# schematEle.net
KiCad netlist of a schematic drawn in EAGLE
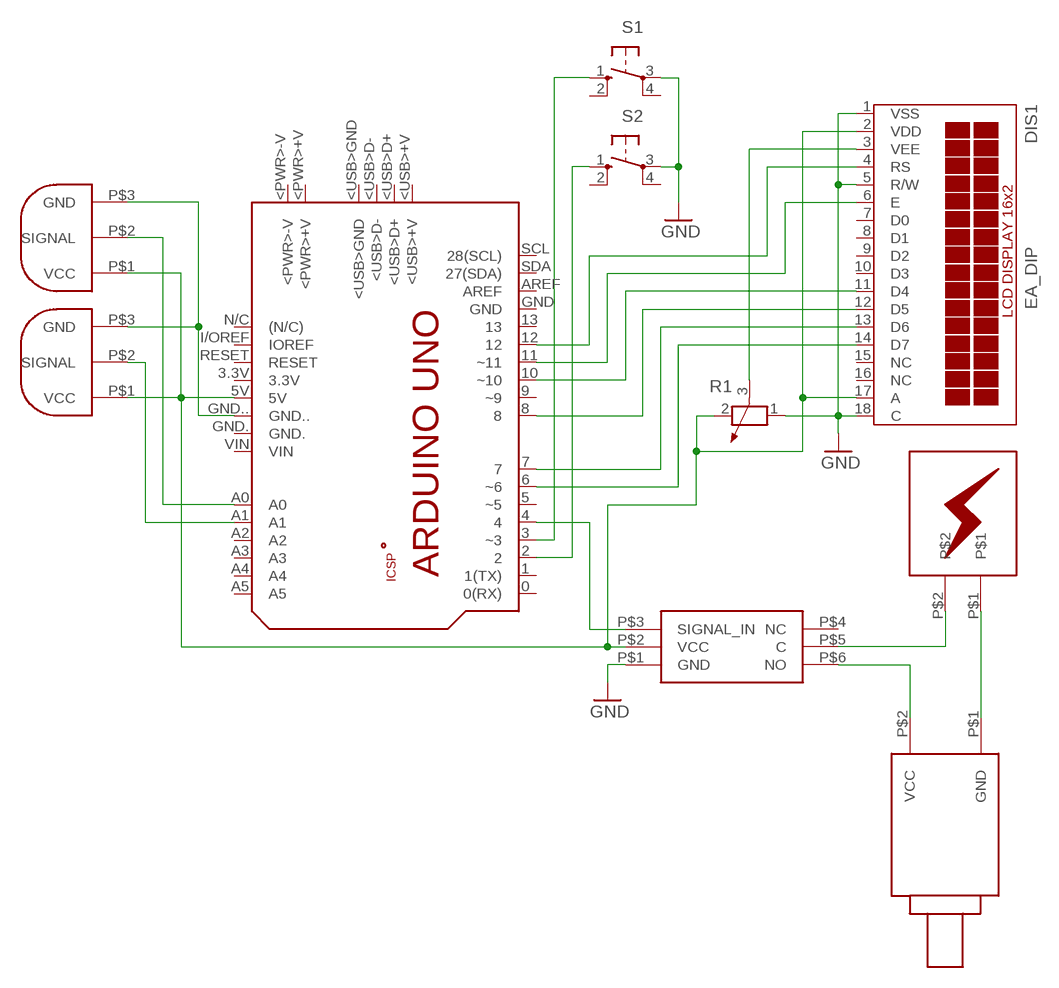
[diagram p0: schematic, sheet 1]

(export (version "E")
  (design (tool "Eeschema 10.0.6"))
  (components
    (comp (ref "DIS1")
      (value "EA_DIP")
      (footprint "eagle-import:EA_DIP")
      (libsource (lib "eagle-import") (part "EA_DIP"))
    )
    (comp (ref "PCB1")
      (value "ARDUINO_UNO")
      (footprint "eagle-import:ARDUINO_UNO")
      (libsource (lib "eagle-import") (part "ARDUINO_UNO"))
    )
    (comp (ref "R1")
      (value "POTENTIOMETER_PT-10")
      (footprint "eagle-import:PT-10")
      (libsource (lib "eagle-import") (part "POTENTIOMETER_PT-10"))
    )
    (comp (ref "RELAY")
      (value "RELAY")
      (footprint "eagle-import:RELAY")
      (libsource (lib "eagle-import") (part "RELAY"))
    )
    (comp (ref "S1")
      (value "10-XX")
      (footprint "eagle-import:B3F-10XX")
      (fields (field (name "MPN") "B3F-1000"))
      (libsource (lib "eagle-import") (part "10-XX"))
    )
    (comp (ref "S2")
      (value "10-XX")
      (footprint "eagle-import:B3F-10XX")
      (fields (field (name "MPN") "B3F-1000"))
      (libsource (lib "eagle-import") (part "10-XX"))
    )
    (comp (ref "U$1")
      (value "POWSOURCE")
      (footprint "eagle-import:SOURCE")
      (libsource (lib "eagle-import") (part "POWSOURCE"))
    )
    (comp (ref "U$2")
      (value "LM35")
      (footprint "eagle-import:LM35")
      (libsource (lib "eagle-import") (part "LM35"))
    )
    (comp (ref "U$3")
      (value "LM35")
      (footprint "eagle-import:LM35")
      (libsource (lib "eagle-import") (part "LM35"))
    )
    (comp (ref "U$4")
      (value "MOTOR")
      (footprint "eagle-import:MOTOR")
      (libsource (lib "eagle-import") (part "MOTOR"))
    )
  )
  (nets
    (net (code "1") (name "GND") (class "Default")
      (node (ref "DIS1") (pin "1") (pinfunction "VSS_1") (pintype "power_in"))
      (node (ref "DIS1") (pin "18") (pinfunction "C_18") (pintype "passive"))
      (node (ref "DIS1") (pin "5") (pinfunction "R/W_5") (pintype "input"))
      (node (ref "R1") (pin "1") (pinfunction "1_1") (pintype "passive"))
      (node (ref "RELAY") (pin "P$1") (pinfunction "GND_P$1") (pintype "bidirectional"))
      (node (ref "S1") (pin "3") (pinfunction "P_3") (pintype "passive"))
      (node (ref "S2") (pin "3") (pinfunction "P_3") (pintype "passive"))
    )
    (net (code "2") (name "Net-(DIS1-A)") (class "Default")
      (node (ref "DIS1") (pin "17") (pinfunction "A_17") (pintype "passive"))
      (node (ref "DIS1") (pin "2") (pinfunction "VDD_2") (pintype "power_in"))
      (node (ref "PCB1") (pin "5V") (pinfunction "5V_5V") (pintype "bidirectional"))
      (node (ref "R1") (pin "2") (pinfunction "2_2") (pintype "passive"))
      (node (ref "RELAY") (pin "P$2") (pinfunction "VCC_P$2") (pintype "bidirectional"))
      (node (ref "U$2") (pin "P$1") (pinfunction "VCC_P$1") (pintype "bidirectional"))
      (node (ref "U$3") (pin "P$1") (pinfunction "VCC_P$1") (pintype "bidirectional"))
    )
    (net (code "3") (name "Net-(DIS1-D4)") (class "Default")
      (node (ref "DIS1") (pin "11") (pinfunction "D4_11") (pintype "input"))
      (node (ref "PCB1") (pin "10") (pinfunction "~{10}_10") (pintype "bidirectional"))
    )
    (net (code "4") (name "Net-(DIS1-D5)") (class "Default")
      (node (ref "DIS1") (pin "12") (pinfunction "D5_12") (pintype "input"))
      (node (ref "PCB1") (pin "8") (pinfunction "8_8") (pintype "bidirectional"))
    )
    (net (code "5") (name "Net-(DIS1-D6)") (class "Default")
      (node (ref "DIS1") (pin "13") (pinfunction "D6_13") (pintype "input"))
      (node (ref "PCB1") (pin "7") (pinfunction "7_7") (pintype "bidirectional"))
    )
    (net (code "6") (name "Net-(DIS1-D7)") (class "Default")
      (node (ref "DIS1") (pin "14") (pinfunction "D7_14") (pintype "input"))
      (node (ref "PCB1") (pin "6") (pinfunction "~{6}_6") (pintype "bidirectional"))
    )
    (net (code "7") (name "Net-(DIS1-E)") (class "Default")
      (node (ref "DIS1") (pin "6") (pinfunction "E_6") (pintype "input"))
      (node (ref "PCB1") (pin "11") (pinfunction "~{11}_11") (pintype "bidirectional"))
    )
    (net (code "8") (name "Net-(DIS1-RS)") (class "Default")
      (node (ref "DIS1") (pin "4") (pinfunction "RS_4") (pintype "input"))
      (node (ref "PCB1") (pin "12") (pinfunction "12_12") (pintype "bidirectional"))
    )
    (net (code "9") (name "Net-(DIS1-VEE)") (class "Default")
      (node (ref "DIS1") (pin "3") (pinfunction "VEE_3") (pintype "power_in"))
      (node (ref "R1") (pin "3") (pinfunction "3_3") (pintype "passive"))
    )
    (net (code "10") (name "Net-(PCB1-~{3})") (class "Default")
      (node (ref "PCB1") (pin "3") (pinfunction "~{3}_3") (pintype "bidirectional"))
      (node (ref "S1") (pin "1") (pinfunction "S_1") (pintype "passive"))
    )
    (net (code "11") (name "Net-(RELAY-C)") (class "Default")
      (node (ref "RELAY") (pin "P$5") (pinfunction "C_P$5") (pintype "bidirectional"))
      (node (ref "U$1") (pin "P$2") (pinfunction "P$2_P$2") (pintype "bidirectional"))
    )
    (net (code "12") (name "Net-(RELAY-NO)") (class "Default")
      (node (ref "RELAY") (pin "P$6") (pinfunction "NO_P$6") (pintype "bidirectional"))
      (node (ref "U$4") (pin "P$2") (pinfunction "VCC_P$2") (pintype "bidirectional"))
    )
    (net (code "13") (name "Net-(RELAY-SIGNAL_IN)") (class "Default")
      (node (ref "PCB1") (pin "4") (pinfunction "4_4") (pintype "bidirectional"))
      (node (ref "RELAY") (pin "P$3") (pinfunction "SIGNAL_IN_P$3") (pintype "bidirectional"))
    )
    (net (code "14") (name "Net-(S2-S)") (class "Default")
      (node (ref "PCB1") (pin "2") (pinfunction "2_2") (pintype "bidirectional"))
      (node (ref "S2") (pin "1") (pinfunction "S_1") (pintype "passive"))
    )
    (net (code "15") (name "Net-(U$2-GND)") (class "Default")
      (node (ref "PCB1") (pin "GND..") (pinfunction "GND.._GND..") (pintype "bidirectional"))
      (node (ref "U$2") (pin "P$3") (pinfunction "GND_P$3") (pintype "bidirectional"))
      (node (ref "U$3") (pin "P$3") (pinfunction "GND_P$3") (pintype "bidirectional"))
    )
    (net (code "16") (name "Net-(U$2-SIGNAL)") (class "Default")
      (node (ref "PCB1") (pin "A0") (pinfunction "A0_A0") (pintype "bidirectional"))
      (node (ref "U$2") (pin "P$2") (pinfunction "SIGNAL_P$2") (pintype "bidirectional"))
    )
    (net (code "17") (name "Net-(U$3-SIGNAL)") (class "Default")
      (node (ref "PCB1") (pin "A1") (pinfunction "A1_A1") (pintype "bidirectional"))
      (node (ref "U$3") (pin "P$2") (pinfunction "SIGNAL_P$2") (pintype "bidirectional"))
    )
    (net (code "18") (name "Net-(U$4-GND)") (class "Default")
      (node (ref "U$1") (pin "P$1") (pinfunction "P$1_P$1") (pintype "bidirectional"))
      (node (ref "U$4") (pin "P$1") (pinfunction "GND_P$1") (pintype "bidirectional"))
    )
    (net (code "19") (name "unconnected-(DIS1-D0-Pad7)") (class "Default")
      (node (ref "DIS1") (pin "7") (pinfunction "D0_7") (pintype "input"))
    )
    (net (code "20") (name "unconnected-(DIS1-D1-Pad8)") (class "Default")
      (node (ref "DIS1") (pin "8") (pinfunction "D1_8") (pintype "input"))
    )
    (net (code "21") (name "unconnected-(DIS1-D2-Pad9)") (class "Default")
      (node (ref "DIS1") (pin "9") (pinfunction "D2_9") (pintype "input"))
    )
    (net (code "22") (name "unconnected-(DIS1-D3-Pad10)") (class "Default")
      (node (ref "DIS1") (pin "10") (pinfunction "D3_10") (pintype "input"))
    )
    (net (code "23") (name "unconnected-(DIS1-NC-Pad15)") (class "Default")
      (node (ref "DIS1") (pin "15") (pinfunction "NC_15") (pintype "no_connect"))
    )
    (net (code "24") (name "unconnected-(DIS1-NC-Pad16)") (class "Default")
      (node (ref "DIS1") (pin "16") (pinfunction "NC_16") (pintype "no_connect"))
    )
    (net (code "25") (name "unconnected-(PCB1-(N{slash}C)-PadN{slash}C)") (class "Default")
      (node (ref "PCB1") (pin "N/C") (pinfunction "(N/C)_N/C") (pintype "bidirectional"))
    )
    (net (code "26") (name "unconnected-(PCB1-0(RX)-Pad0)") (class "Default")
      (node (ref "PCB1") (pin "0") (pinfunction "0(RX)_0") (pintype "bidirectional"))
    )
    (net (code "27") (name "unconnected-(PCB1-1(TX)-Pad1)") (class "Default")
      (node (ref "PCB1") (pin "1") (pinfunction "1(TX)_1") (pintype "bidirectional"))
    )
    (net (code "28") (name "unconnected-(PCB1-27(SDA)-PadSDA)") (class "Default")
      (node (ref "PCB1") (pin "SDA") (pinfunction "27(SDA)_SDA") (pintype "bidirectional"))
    )
    (net (code "29") (name "unconnected-(PCB1-28(SCL)-PadSCL)") (class "Default")
      (node (ref "PCB1") (pin "SCL") (pinfunction "28(SCL)_SCL") (pintype "bidirectional"))
    )
    (net (code "30") (name "unconnected-(PCB1-IOREF-PadI{slash}OREF)") (class "Default")
      (node (ref "PCB1") (pin "I/OREF") (pinfunction "IOREF_I/OREF") (pintype "bidirectional"))
    )
    (net (code "31") (name "unconnected-(PCB1-Pad+5V)") (class "Default")
      (node (ref "PCB1") (pin "+5V") (pinfunction "+5V_+5V") (pintype "bidirectional"))
    )
    (net (code "32") (name "unconnected-(PCB1-Pad3.3V)") (class "Default")
      (node (ref "PCB1") (pin "3.3V") (pinfunction "3.3V_3.3V") (pintype "bidirectional"))
    )
    (net (code "33") (name "unconnected-(PCB1-Pad13)") (class "Default")
      (node (ref "PCB1") (pin "13") (pinfunction "13_13") (pintype "bidirectional"))
    )
    (net (code "34") (name "unconnected-(PCB1-Pad<PWR>+V)") (class "Default")
      (node (ref "PCB1") (pin "<PWR>+V") (pinfunction "<PWR>+V_<PWR>+V") (pintype "bidirectional"))
    )
    (net (code "35") (name "unconnected-(PCB1-Pad<PWR>-V)") (class "Default")
      (node (ref "PCB1") (pin "<PWR>-V") (pinfunction "<PWR>-V_<PWR>-V") (pintype "bidirectional"))
    )
    (net (code "36") (name "unconnected-(PCB1-Pad<USB>+V)") (class "Default")
      (node (ref "PCB1") (pin "<USB>+V") (pinfunction "<USB>+V_<USB>+V") (pintype "bidirectional"))
    )
    (net (code "37") (name "unconnected-(PCB1-Pad<USB>D+)") (class "Default")
      (node (ref "PCB1") (pin "<USB>D+") (pinfunction "<USB>D+_<USB>D+") (pintype "bidirectional"))
    )
    (net (code "38") (name "unconnected-(PCB1-Pad<USB>D-)") (class "Default")
      (node (ref "PCB1") (pin "<USB>D-") (pinfunction "<USB>D-_<USB>D-") (pintype "bidirectional"))
    )
    (net (code "39") (name "unconnected-(PCB1-Pad<USB>GND)") (class "Default")
      (node (ref "PCB1") (pin "<USB>GND") (pinfunction "<USB>GND_<USB>GND") (pintype "bidirectional"))
    )
    (net (code "40") (name "unconnected-(PCB1-PadA2)") (class "Default")
      (node (ref "PCB1") (pin "A2") (pinfunction "A2_A2") (pintype "bidirectional"))
    )
    (net (code "41") (name "unconnected-(PCB1-PadA3)") (class "Default")
      (node (ref "PCB1") (pin "A3") (pinfunction "A3_A3") (pintype "bidirectional"))
    )
    (net (code "42") (name "unconnected-(PCB1-PadA4)") (class "Default")
      (node (ref "PCB1") (pin "A4") (pinfunction "A4_A4") (pintype "bidirectional"))
    )
    (net (code "43") (name "unconnected-(PCB1-PadA5)") (class "Default")
      (node (ref "PCB1") (pin "A5") (pinfunction "A5_A5") (pintype "bidirectional"))
    )
    (net (code "44") (name "unconnected-(PCB1-PadAREF)") (class "Default")
      (node (ref "PCB1") (pin "AREF") (pinfunction "AREF_AREF") (pintype "bidirectional"))
    )
    (net (code "45") (name "unconnected-(PCB1-PadGND)") (class "Default")
      (node (ref "PCB1") (pin "GND") (pinfunction "GND_GND") (pintype "bidirectional"))
    )
    (net (code "46") (name "unconnected-(PCB1-PadGND.)") (class "Default")
      (node (ref "PCB1") (pin "GND.") (pinfunction "GND._GND.") (pintype "bidirectional"))
    )
    (net (code "47") (name "unconnected-(PCB1-PadGND_)") (class "Default")
      (node (ref "PCB1") (pin "GND_") (pinfunction "GND__GND_") (pintype "bidirectional"))
    )
    (net (code "48") (name "unconnected-(PCB1-PadMISO)") (class "Default")
      (node (ref "PCB1") (pin "MISO") (pinfunction "MISO_MISO") (pintype "bidirectional"))
    )
    (net (code "49") (name "unconnected-(PCB1-PadMOSI)") (class "Default")
      (node (ref "PCB1") (pin "MOSI") (pinfunction "MOSI_MOSI") (pintype "bidirectional"))
    )
    (net (code "50") (name "unconnected-(PCB1-PadRESET)") (class "Default")
      (node (ref "PCB1") (pin "RESET") (pinfunction "RESET_RESET") (pintype "bidirectional"))
    )
    (net (code "51") (name "unconnected-(PCB1-PadRESET.)") (class "Default")
      (node (ref "PCB1") (pin "RESET.") (pinfunction "RESET._RESET.") (pintype "bidirectional"))
    )
    (net (code "52") (name "unconnected-(PCB1-PadSCK)") (class "Default")
      (node (ref "PCB1") (pin "SCK") (pinfunction "SCK_SCK") (pintype "bidirectional"))
    )
    (net (code "53") (name "unconnected-(PCB1-PadVIN)") (class "Default")
      (node (ref "PCB1") (pin "VIN") (pinfunction "VIN_VIN") (pintype "bidirectional"))
    )
    (net (code "54") (name "unconnected-(PCB1-~{5}-Pad5)") (class "Default")
      (node (ref "PCB1") (pin "5") (pinfunction "~{5}_5") (pintype "bidirectional"))
    )
    (net (code "55") (name "unconnected-(PCB1-~{9}-Pad9)") (class "Default")
      (node (ref "PCB1") (pin "9") (pinfunction "~{9}_9") (pintype "bidirectional"))
    )
    (net (code "56") (name "unconnected-(RELAY-NC-PadP$4)") (class "Default")
      (node (ref "RELAY") (pin "P$4") (pinfunction "NC_P$4") (pintype "bidirectional"))
    )
    (net (code "57") (name "unconnected-(S1-P1-Pad4)") (class "Default")
      (node (ref "S1") (pin "4") (pinfunction "P1_4") (pintype "passive"))
    )
    (net (code "58") (name "unconnected-(S1-S1-Pad2)") (class "Default")
      (node (ref "S1") (pin "2") (pinfunction "S1_2") (pintype "passive"))
    )
    (net (code "59") (name "unconnected-(S2-P1-Pad4)") (class "Default")
      (node (ref "S2") (pin "4") (pinfunction "P1_4") (pintype "passive"))
    )
    (net (code "60") (name "unconnected-(S2-S1-Pad2)") (class "Default")
      (node (ref "S2") (pin "2") (pinfunction "S1_2") (pintype "passive"))
    )
  )
)
